# 464421_22-01_BBP.net
KiCad netlist of a schematic drawn in Altium Designer
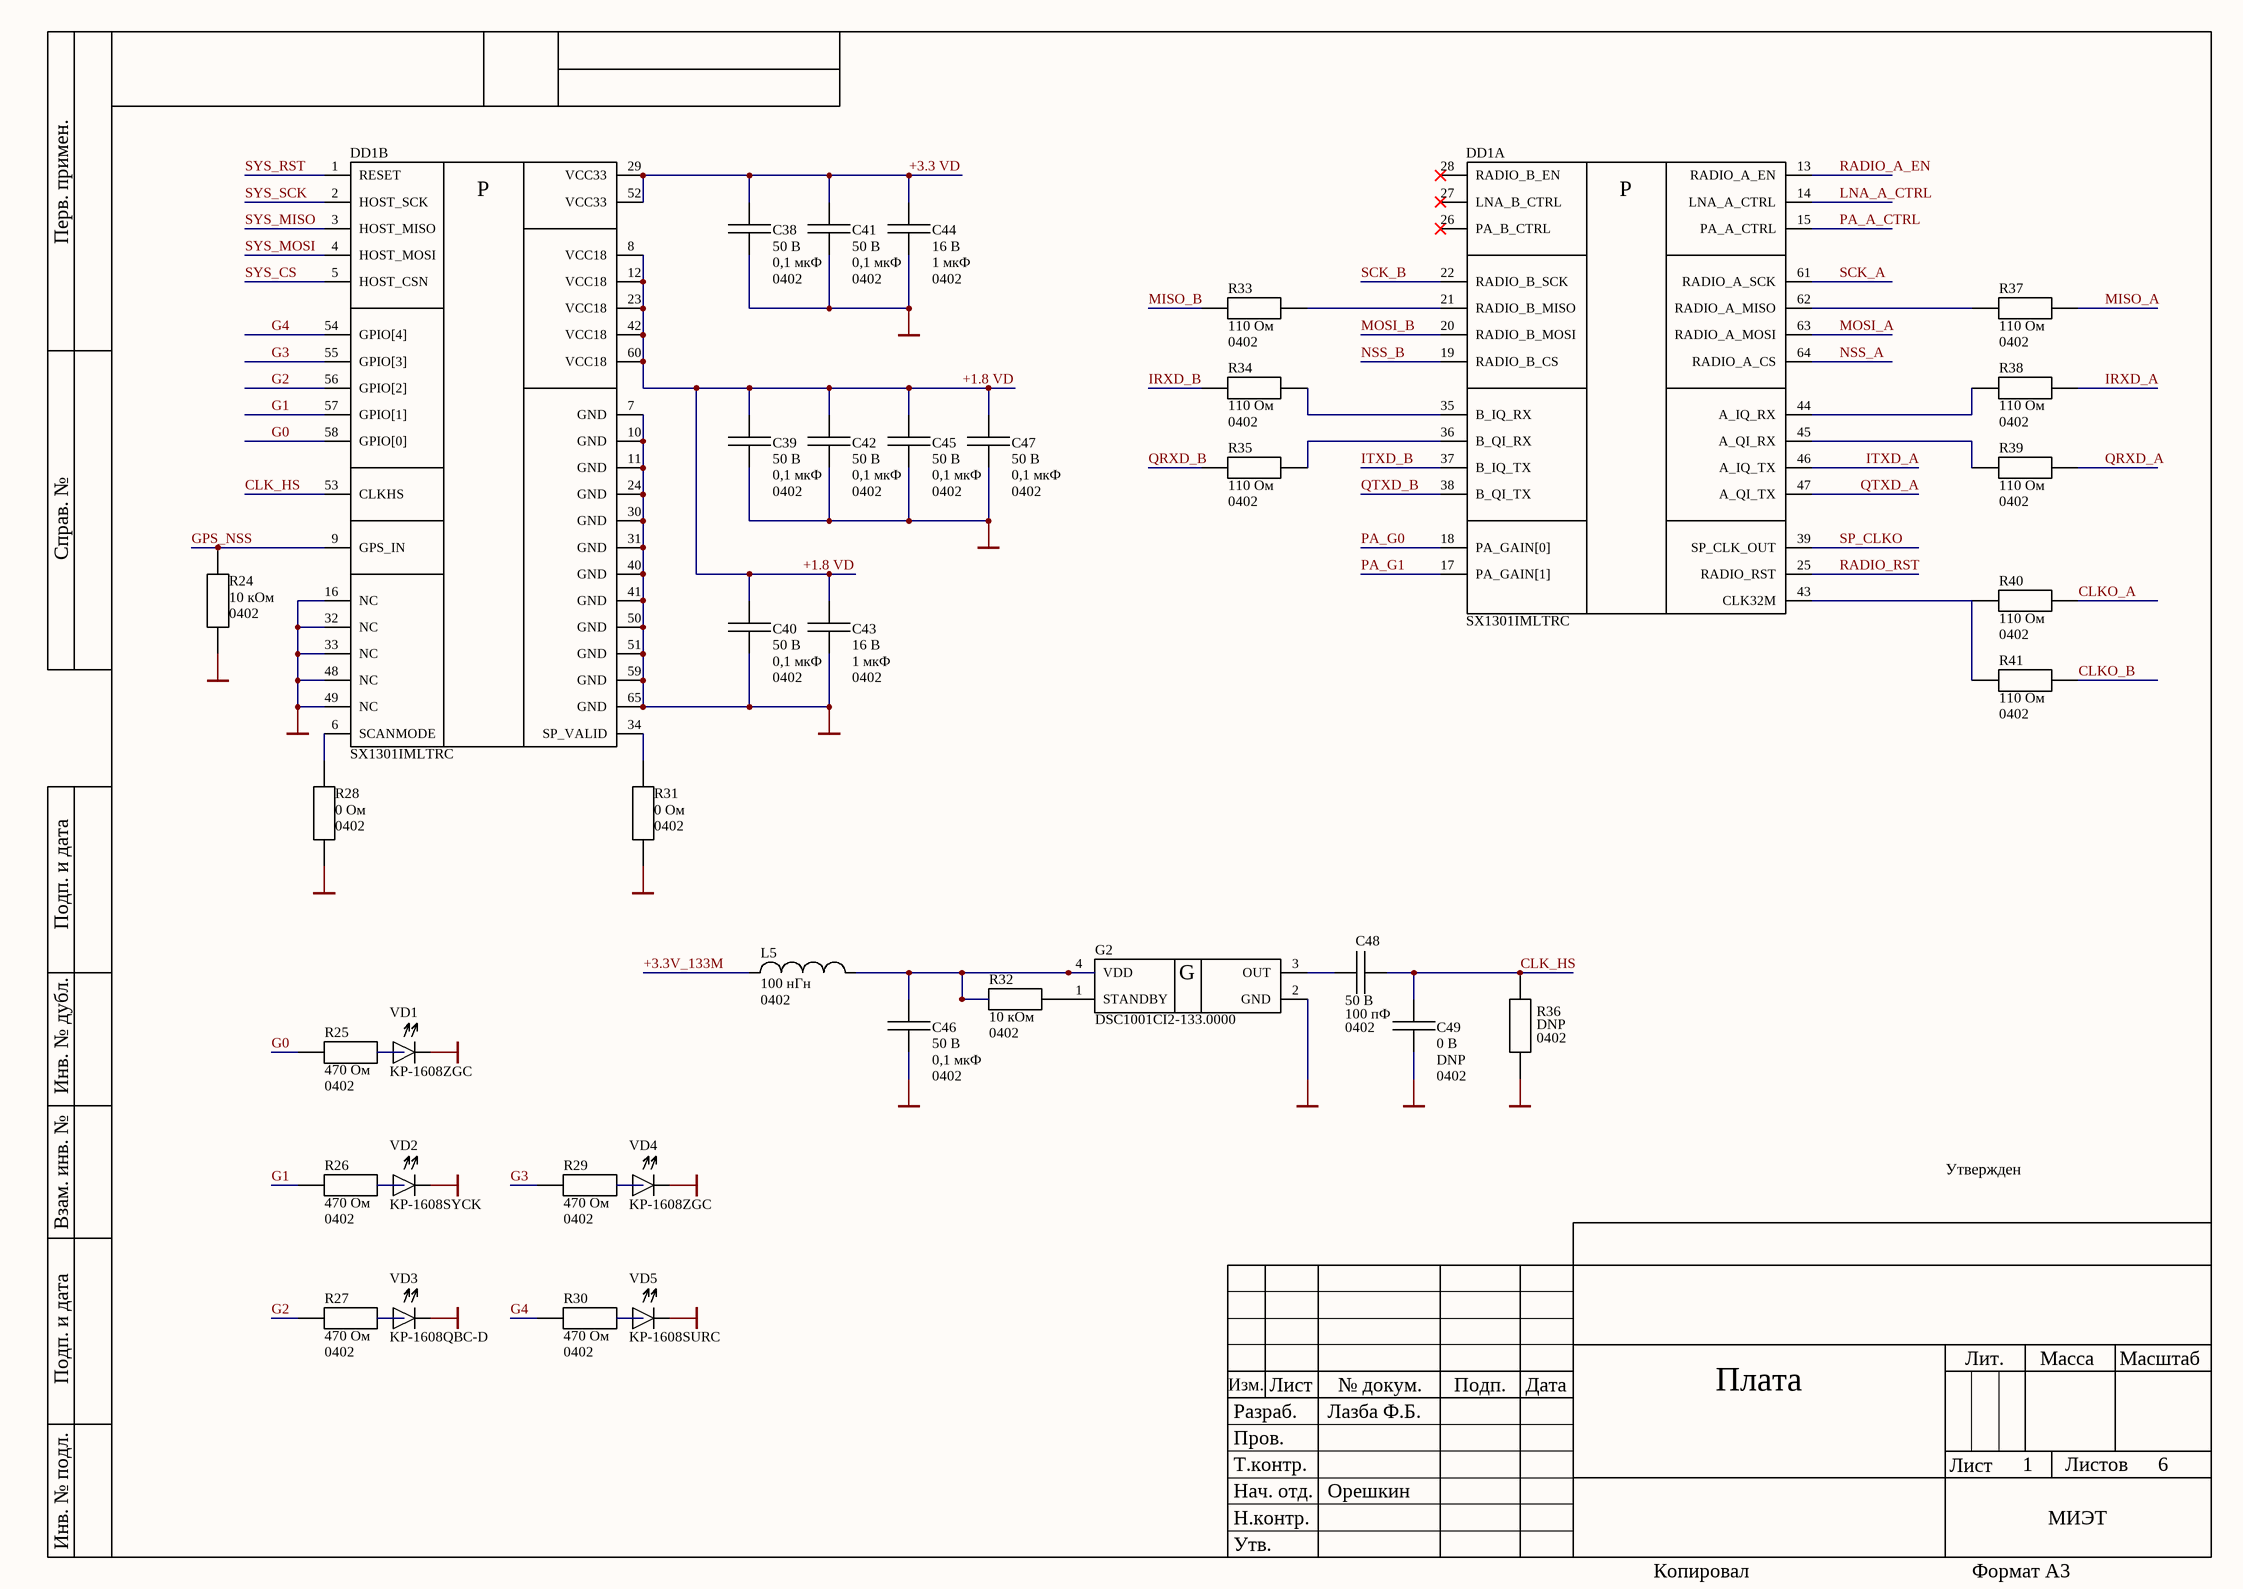
[diagram p0: МПСУ.464421.22-01 BBP.SchDoc]

(export (version "E")
  (design (tool "Eeschema 10.0.6"))
  (components
    (comp (ref "C38")
      (value "0,1 мкФ")
      (footprint "Passive_V2_0:CAPC100X50X55L20N")
      (description "Capacitor 0402")
      (fields
        (field (name "PARTNUMBER") "GRM155R71H104KE14J")
        (field (name "MANUFACTURER") "Murata")
        (field (name "PEAK_CONDITION") "50 В")
        (field (name "PACKAGE") "0402")
        (field (name "DESIGNER") "Свидерский")
      )
      (libsource (lib "Passive_V2_0") (part "C 0402"))
    )
    (comp (ref "C39")
      (value "0,1 мкФ")
      (footprint "Passive_V2_0:CAPC100X50X55L20N")
      (description "Capacitor 0402")
      (fields
        (field (name "PARTNUMBER") "GRM155R71H104KE14J")
        (field (name "MANUFACTURER") "Murata")
        (field (name "PEAK_CONDITION") "50 В")
        (field (name "PACKAGE") "0402")
        (field (name "DESIGNER") "Свидерский")
      )
      (libsource (lib "Passive_V2_0") (part "C 0402"))
    )
    (comp (ref "C40")
      (value "0,1 мкФ")
      (footprint "Passive_V2_0:CAPC100X50X55L20N")
      (description "Capacitor 0402")
      (fields
        (field (name "PARTNUMBER") "GRM155R71H104KE14J")
        (field (name "MANUFACTURER") "Murata")
        (field (name "PEAK_CONDITION") "50 В")
        (field (name "PACKAGE") "0402")
        (field (name "DESIGNER") "Свидерский")
      )
      (libsource (lib "Passive_V2_0") (part "C 0402"))
    )
    (comp (ref "C41")
      (value "0,1 мкФ")
      (footprint "Passive_V2_0:CAPC100X50X55L20N")
      (description "Capacitor 0402")
      (fields
        (field (name "PARTNUMBER") "GRM155R71H104KE14J")
        (field (name "MANUFACTURER") "Murata")
        (field (name "PEAK_CONDITION") "50 В")
        (field (name "PACKAGE") "0402")
        (field (name "DESIGNER") "Свидерский")
      )
      (libsource (lib "Passive_V2_0") (part "C 0402"))
    )
    (comp (ref "C42")
      (value "0,1 мкФ")
      (footprint "Passive_V2_0:CAPC100X50X55L20N")
      (description "Capacitor 0402")
      (fields
        (field (name "PARTNUMBER") "GRM155R71H104KE14J")
        (field (name "MANUFACTURER") "Murata")
        (field (name "PEAK_CONDITION") "50 В")
        (field (name "PACKAGE") "0402")
        (field (name "DESIGNER") "Свидерский")
      )
      (libsource (lib "Passive_V2_0") (part "C 0402"))
    )
    (comp (ref "C43")
      (value "1 мкФ")
      (footprint "Passive_V2_0:CAPC100X50X55L20N")
      (description "Capacitor 0402")
      (fields
        (field (name "PARTNUMBER") "GRM155R61C105KA12D")
        (field (name "MANUFACTURER") "Murata")
        (field (name "PEAK_CONDITION") "16 В")
        (field (name "PACKAGE") "0402")
        (field (name "DESIGNER") "Свидерский")
      )
      (libsource (lib "Passive_V2_0") (part "C 0402"))
    )
    (comp (ref "C44")
      (value "1 мкФ")
      (footprint "Passive_V2_0:CAPC100X50X55L20N")
      (description "Capacitor 0402")
      (fields
        (field (name "PARTNUMBER") "GRM155R61C105KA12D")
        (field (name "MANUFACTURER") "Murata")
        (field (name "PEAK_CONDITION") "16 В")
        (field (name "PACKAGE") "0402")
        (field (name "DESIGNER") "Свидерский")
      )
      (libsource (lib "Passive_V2_0") (part "C 0402"))
    )
    (comp (ref "C45")
      (value "0,1 мкФ")
      (footprint "Passive_V2_0:CAPC100X50X55L20N")
      (description "Capacitor 0402")
      (fields
        (field (name "PARTNUMBER") "GRM155R71H104KE14J")
        (field (name "MANUFACTURER") "Murata")
        (field (name "PEAK_CONDITION") "50 В")
        (field (name "PACKAGE") "0402")
        (field (name "DESIGNER") "Свидерский")
      )
      (libsource (lib "Passive_V2_0") (part "C 0402"))
    )
    (comp (ref "C46")
      (value "0,1 мкФ")
      (footprint "Passive_V2_0:CAPC100X50X55L20N")
      (description "Capacitor 0402")
      (fields
        (field (name "PARTNUMBER") "GRM155R71H104KE14J")
        (field (name "MANUFACTURER") "Murata")
        (field (name "PEAK_CONDITION") "50 В")
        (field (name "PACKAGE") "0402")
        (field (name "DESIGNER") "Свидерский")
      )
      (libsource (lib "Passive_V2_0") (part "C 0402"))
    )
    (comp (ref "C47")
      (value "0,1 мкФ")
      (footprint "Passive_V2_0:CAPC100X50X55L20N")
      (description "Capacitor 0402")
      (fields
        (field (name "PARTNUMBER") "GRM155R71H104KE14J")
        (field (name "MANUFACTURER") "Murata")
        (field (name "PEAK_CONDITION") "50 В")
        (field (name "PACKAGE") "0402")
        (field (name "DESIGNER") "Свидерский")
      )
      (libsource (lib "Passive_V2_0") (part "C 0402"))
    )
    (comp (ref "C48")
      (value "100 пФ")
      (footprint "Passive_V2_0:CAPC100X50X55L20N")
      (description "Capacitor 0402")
      (fields
        (field (name "PARTNUMBER") "GRM1555C1H101JZ01D")
        (field (name "MANUFACTURER") "Murata")
        (field (name "PEAK_CONDITION") "50 В")
        (field (name "PACKAGE") "0402")
        (field (name "DESIGNER") "Свидерский")
      )
      (libsource (lib "Passive_V2_0") (part "C 0402"))
    )
    (comp (ref "C49")
      (value "DNP")
      (footprint "Passive_V2_0:CAPC100X50X55L20N")
      (description "Capacitor 0402")
      (fields
        (field (name "TOLERANCE") "0 %")
        (field (name "PEAK_CONDITION") "0 В")
        (field (name "PACKAGE") "0402")
        (field (name "Comment") "DNP 0402")
        (field (name "DESIGNER") "Свидерский")
      )
      (libsource (lib "Passive_V2_0") (part "C 0402"))
    )
    (comp (ref "DD1")
      (value "SX1301IMLTRC")
      (footprint "IC_V2_0:SX1301IMLTRC")
      (description "LoRa Core™ Digital Baseband Chip for outdoor LoRaWAN® network macro gateways")
      (fields
        (field (name "MANUFACTURER") "Semtech")
        (field (name "PARTNUMBER") "SX1301IMLTRC")
        (field (name "DESIGNER") "Лазба")
      )
      (libsource (lib "IC_V2_0") (part "SX1301IMLTRC"))
    )
    (comp (ref "G2")
      (value "DSC1001CI2-133.0000")
      (footprint "IC_V2_0:DSC1001CI2")
      (description "1.8V-3.3V Low-Power Precision CMOS Oscillators 1-150 MHz Family")
      (fields
        (field (name "MANUFACTURER") "Microchip")
        (field (name "PARTNUMBER") "DSC1001CI2-133.0000")
        (field (name "DESIGNER") "Лазба")
      )
      (libsource (lib "IC_V2_0") (part "DSC1001/3/4***-***.****"))
    )
    (comp (ref "L5")
      (value "100 нГн")
      (footprint "Passive_V2_0:INDC100X50X60L10N")
      (description "Inductor 0402")
      (fields
        (field (name "PARTNUMBER") "LQG15HNR10J02D")
        (field (name "TOLERANCE") "5 %")
        (field (name "PACKAGE") "0402")
        (field (name "DESIGNER") "Свидерский")
      )
      (libsource (lib "Passive_V2_0") (part "L 0402"))
    )
    (comp (ref "R24")
      (value "10 кОм")
      (footprint "Passive_V2_0:RESC100X50X40L25N")
      (description "Resistor 0402")
      (fields
        (field (name "PARTNUMBER") "RI0402L103JT")
        (field (name "TOLERANCE") "5 %")
        (field (name "PACKAGE") "0402")
        (field (name "DESIGNER") "Свидерский")
      )
      (libsource (lib "") (part "R 0402_1"))
    )
    (comp (ref "R25")
      (value "470 Ом")
      (footprint "Passive_V2_0:RESC100X50X40L25N")
      (description "Resistor 0402")
      (fields
        (field (name "PARTNUMBER") "RI0402L471JT")
        (field (name "TOLERANCE") "5 %")
        (field (name "PACKAGE") "0402")
        (field (name "DESIGNER") "Свидерский")
      )
      (libsource (lib "Passive_V2_0") (part "R 0402"))
    )
    (comp (ref "R26")
      (value "470 Ом")
      (footprint "Passive_V2_0:RESC100X50X40L25N")
      (description "Resistor 0402")
      (fields
        (field (name "PARTNUMBER") "RI0402L471JT")
        (field (name "TOLERANCE") "5 %")
        (field (name "PACKAGE") "0402")
        (field (name "DESIGNER") "Свидерский")
      )
      (libsource (lib "Passive_V2_0") (part "R 0402"))
    )
    (comp (ref "R27")
      (value "470 Ом")
      (footprint "Passive_V2_0:RESC100X50X40L25N")
      (description "Resistor 0402")
      (fields
        (field (name "PARTNUMBER") "RI0402L471JT")
        (field (name "TOLERANCE") "5 %")
        (field (name "PACKAGE") "0402")
        (field (name "DESIGNER") "Свидерский")
      )
      (libsource (lib "Passive_V2_0") (part "R 0402"))
    )
    (comp (ref "R28")
      (value "0 Ом")
      (footprint "Passive_V2_0:RESC100X50X40L25N")
      (description "Resistor 0402")
      (fields
        (field (name "PARTNUMBER") "RI0402L000JT")
        (field (name "TOLERANCE") "5 %")
        (field (name "PACKAGE") "0402")
        (field (name "DESIGNER") "Свидерский")
      )
      (libsource (lib "") (part "R 0402_1"))
    )
    (comp (ref "R29")
      (value "470 Ом")
      (footprint "Passive_V2_0:RESC100X50X40L25N")
      (description "Resistor 0402")
      (fields
        (field (name "PARTNUMBER") "RI0402L471JT")
        (field (name "TOLERANCE") "5 %")
        (field (name "PACKAGE") "0402")
        (field (name "DESIGNER") "Свидерский")
      )
      (libsource (lib "Passive_V2_0") (part "R 0402"))
    )
    (comp (ref "R30")
      (value "470 Ом")
      (footprint "Passive_V2_0:RESC100X50X40L25N")
      (description "Resistor 0402")
      (fields
        (field (name "PARTNUMBER") "RI0402L471JT")
        (field (name "TOLERANCE") "5 %")
        (field (name "PACKAGE") "0402")
        (field (name "DESIGNER") "Свидерский")
      )
      (libsource (lib "Passive_V2_0") (part "R 0402"))
    )
    (comp (ref "R31")
      (value "0 Ом")
      (footprint "Passive_V2_0:RESC100X50X40L25N")
      (description "Resistor 0402")
      (fields
        (field (name "PARTNUMBER") "RI0402L000JT")
        (field (name "TOLERANCE") "5 %")
        (field (name "PACKAGE") "0402")
        (field (name "DESIGNER") "Свидерский")
      )
      (libsource (lib "") (part "R 0402_1"))
    )
    (comp (ref "R32")
      (value "10 кОм")
      (footprint "Passive_V2_0:RESC100X50X40L25N")
      (description "Resistor 0402")
      (fields
        (field (name "PARTNUMBER") "RI0402L103JT")
        (field (name "TOLERANCE") "5 %")
        (field (name "PACKAGE") "0402")
        (field (name "DESIGNER") "Свидерский")
      )
      (libsource (lib "Passive_V2_0") (part "R 0402"))
    )
    (comp (ref "R33")
      (value "110 Ом")
      (footprint "Passive_V2_0:RESC100X50X40L25N")
      (description "Resistor 0402")
      (fields
        (field (name "PARTNUMBER") "RC-02U111JT")
        (field (name "TOLERANCE") "5 %")
        (field (name "PACKAGE") "0402")
        (field (name "DESIGNER") "Свидерский")
      )
      (libsource (lib "Passive_V2_0") (part "R 0402"))
    )
    (comp (ref "R34")
      (value "110 Ом")
      (footprint "Passive_V2_0:RESC100X50X40L25N")
      (description "Resistor 0402")
      (fields
        (field (name "PARTNUMBER") "RC-02U111JT")
        (field (name "TOLERANCE") "5 %")
        (field (name "PACKAGE") "0402")
        (field (name "DESIGNER") "Свидерский")
      )
      (libsource (lib "Passive_V2_0") (part "R 0402"))
    )
    (comp (ref "R35")
      (value "110 Ом")
      (footprint "Passive_V2_0:RESC100X50X40L25N")
      (description "Resistor 0402")
      (fields
        (field (name "PARTNUMBER") "RC-02U111JT")
        (field (name "TOLERANCE") "5 %")
        (field (name "PACKAGE") "0402")
        (field (name "DESIGNER") "Свидерский")
      )
      (libsource (lib "Passive_V2_0") (part "R 0402"))
    )
    (comp (ref "R36")
      (value "DNP")
      (footprint "Passive_V2_0:RESC100X50X40L25N")
      (description "Resistor 0402")
      (fields
        (field (name "TOLERANCE") "0 %")
        (field (name "PACKAGE") "0402")
        (field (name "Comment") "DNP 0402")
        (field (name "DESIGNER") "Свидерский")
      )
      (libsource (lib "") (part "R 0402_2"))
    )
    (comp (ref "R37")
      (value "110 Ом")
      (footprint "Passive_V2_0:RESC100X50X40L25N")
      (description "Resistor 0402")
      (fields
        (field (name "PARTNUMBER") "RC-02U111JT")
        (field (name "TOLERANCE") "5 %")
        (field (name "PACKAGE") "0402")
        (field (name "DESIGNER") "Свидерский")
      )
      (libsource (lib "Passive_V2_0") (part "R 0402"))
    )
    (comp (ref "R38")
      (value "110 Ом")
      (footprint "Passive_V2_0:RESC100X50X40L25N")
      (description "Resistor 0402")
      (fields
        (field (name "PARTNUMBER") "RC-02U111JT")
        (field (name "TOLERANCE") "5 %")
        (field (name "PACKAGE") "0402")
        (field (name "DESIGNER") "Свидерский")
      )
      (libsource (lib "Passive_V2_0") (part "R 0402"))
    )
    (comp (ref "R39")
      (value "110 Ом")
      (footprint "Passive_V2_0:RESC100X50X40L25N")
      (description "Resistor 0402")
      (fields
        (field (name "PARTNUMBER") "RC-02U111JT")
        (field (name "TOLERANCE") "5 %")
        (field (name "PACKAGE") "0402")
        (field (name "DESIGNER") "Свидерский")
      )
      (libsource (lib "Passive_V2_0") (part "R 0402"))
    )
    (comp (ref "R40")
      (value "110 Ом")
      (footprint "Passive_V2_0:RESC100X50X40L25N")
      (description "Resistor 0402")
      (fields
        (field (name "PARTNUMBER") "RC-02U111JT")
        (field (name "TOLERANCE") "5 %")
        (field (name "PACKAGE") "0402")
        (field (name "DESIGNER") "Свидерский")
      )
      (libsource (lib "Passive_V2_0") (part "R 0402"))
    )
    (comp (ref "R41")
      (value "110 Ом")
      (footprint "Passive_V2_0:RESC100X50X40L25N")
      (description "Resistor 0402")
      (fields
        (field (name "PARTNUMBER") "RC-02U111JT")
        (field (name "TOLERANCE") "5 %")
        (field (name "PACKAGE") "0402")
        (field (name "DESIGNER") "Свидерский")
      )
      (libsource (lib "Passive_V2_0") (part "R 0402"))
    )
    (comp (ref "VD1")
      (value "KP-1608ZGC")
      (footprint "Discrete_V2_0:KP-1608ZGC")
      (description "1.6X0.8mm SMD CHIP LED LAMP")
      (fields
        (field (name "MANUFACTURER") "Kingbright")
        (field (name "PARTNUMBER") "KP-1608ZGC")
        (field (name "DESIGNER") "Ушакова")
      )
      (libsource (lib "Discrete_V2_0") (part "KP-1608***"))
    )
    (comp (ref "VD2")
      (value "KP-1608SYCK")
      (footprint "Discrete_V2_0:KP-1608ZGC")
      (description "1.6X0.8mm SMD CHIP LED LAMP")
      (fields
        (field (name "MANUFACTURER") "Kingbright")
        (field (name "PARTNUMBER") "KP-1608SYCK")
        (field (name "DESIGNER") "Ушакова")
      )
      (libsource (lib "Discrete_V2_0") (part "KP-1608***"))
    )
    (comp (ref "VD3")
      (value "KP-1608QBC-D")
      (footprint "Discrete_V2_0:KP-1608ZGC")
      (description "1.6X0.8mm SMD CHIP LED LAMP")
      (fields
        (field (name "MANUFACTURER") "Kingbright")
        (field (name "PARTNUMBER") "KP-1608QBC-D")
        (field (name "DESIGNER") "Ушакова")
      )
      (libsource (lib "Discrete_V2_0") (part "KP-1608***"))
    )
    (comp (ref "VD4")
      (value "KP-1608ZGC")
      (footprint "Discrete_V2_0:KP-1608ZGC")
      (description "1.6X0.8mm SMD CHIP LED LAMP")
      (fields
        (field (name "MANUFACTURER") "Kingbright")
        (field (name "PARTNUMBER") "KP-1608ZGC")
        (field (name "DESIGNER") "Ушакова")
      )
      (libsource (lib "Discrete_V2_0") (part "KP-1608***"))
    )
    (comp (ref "VD5")
      (value "KP-1608SURC")
      (footprint "Discrete_V2_0:KP-1608ZGC")
      (description "1.6X0.8mm SMD CHIP LED LAMP")
      (fields
        (field (name "MANUFACTURER") "Kingbright")
        (field (name "PARTNUMBER") "KP-1608SURC")
        (field (name "DESIGNER") "Ушакова")
      )
      (libsource (lib "Discrete_V2_0") (part "KP-1608***"))
    )
  )
  (nets
    (net (code "1") (name "/+1.8 VD") (class "Default")
      (node (ref "C39") (pin "1") (pinfunction "1_1") (pintype "passive"))
      (node (ref "C40") (pin "1") (pinfunction "1_1") (pintype "passive"))
      (node (ref "C42") (pin "1") (pinfunction "1_1") (pintype "passive"))
      (node (ref "C43") (pin "1") (pinfunction "1_1") (pintype "passive"))
      (node (ref "C45") (pin "1") (pinfunction "1_1") (pintype "passive"))
      (node (ref "C47") (pin "1") (pinfunction "1_1") (pintype "passive"))
      (node (ref "DD1") (pin "12") (pinfunction "VCC18_12") (pintype "passive"))
      (node (ref "DD1") (pin "23") (pinfunction "VCC18_23") (pintype "passive"))
      (node (ref "DD1") (pin "42") (pinfunction "VCC18_42") (pintype "passive"))
      (node (ref "DD1") (pin "60") (pinfunction "VCC18_60") (pintype "passive"))
      (node (ref "DD1") (pin "8") (pinfunction "VCC18_8") (pintype "passive"))
    )
    (net (code "2") (name "/+3.3 VD") (class "Default")
      (node (ref "C38") (pin "1") (pinfunction "1_1") (pintype "passive"))
      (node (ref "C41") (pin "1") (pinfunction "1_1") (pintype "passive"))
      (node (ref "C44") (pin "1") (pinfunction "1_1") (pintype "passive"))
      (node (ref "DD1") (pin "29") (pinfunction "VCC33_29") (pintype "passive"))
      (node (ref "DD1") (pin "52") (pinfunction "VCC33_52") (pintype "passive"))
    )
    (net (code "3") (name "/+3.3V_133M") (class "Default")
      (node (ref "L5") (pin "1") (pinfunction "1_1") (pintype "passive"))
    )
    (net (code "4") (name "/CLKO_A") (class "Default")
      (node (ref "R40") (pin "2") (pinfunction "2_2") (pintype "passive"))
    )
    (net (code "5") (name "/CLKO_B") (class "Default")
      (node (ref "R41") (pin "2") (pinfunction "2_2") (pintype "passive"))
    )
    (net (code "6") (name "/CLK_HS") (class "Default")
      (node (ref "C48") (pin "2") (pinfunction "2_2") (pintype "passive"))
      (node (ref "C49") (pin "1") (pinfunction "1_1") (pintype "passive"))
      (node (ref "DD1") (pin "53") (pinfunction "CLKHS_53") (pintype "passive"))
      (node (ref "R36") (pin "1") (pinfunction "1_1") (pintype "passive"))
    )
    (net (code "7") (name "/G0") (class "Default")
      (node (ref "DD1") (pin "58") (pinfunction "GPIO[0]_58") (pintype "passive"))
      (node (ref "R25") (pin "1") (pinfunction "1_1") (pintype "passive"))
    )
    (net (code "8") (name "/G1") (class "Default")
      (node (ref "DD1") (pin "57") (pinfunction "GPIO[1]_57") (pintype "passive"))
      (node (ref "R26") (pin "1") (pinfunction "1_1") (pintype "passive"))
    )
    (net (code "9") (name "/G2") (class "Default")
      (node (ref "DD1") (pin "56") (pinfunction "GPIO[2]_56") (pintype "passive"))
      (node (ref "R27") (pin "1") (pinfunction "1_1") (pintype "passive"))
    )
    (net (code "10") (name "/G3") (class "Default")
      (node (ref "DD1") (pin "55") (pinfunction "GPIO[3]_55") (pintype "passive"))
      (node (ref "R29") (pin "1") (pinfunction "1_1") (pintype "passive"))
    )
    (net (code "11") (name "/G4") (class "Default")
      (node (ref "DD1") (pin "54") (pinfunction "GPIO[4]_54") (pintype "passive"))
      (node (ref "R30") (pin "1") (pinfunction "1_1") (pintype "passive"))
    )
    (net (code "12") (name "/GPS_NSS") (class "Default")
      (node (ref "DD1") (pin "9") (pinfunction "GPS_IN_9") (pintype "passive"))
      (node (ref "R24") (pin "2") (pinfunction "2_2") (pintype "passive"))
    )
    (net (code "13") (name "/IRXD_A") (class "Default")
      (node (ref "R38") (pin "2") (pinfunction "2_2") (pintype "passive"))
    )
    (net (code "14") (name "/IRXD_B") (class "Default")
      (node (ref "R34") (pin "1") (pinfunction "1_1") (pintype "passive"))
    )
    (net (code "15") (name "/ITXD_A") (class "Default")
      (node (ref "DD1") (pin "46") (pinfunction "A_IQ_TX_46") (pintype "passive"))
    )
    (net (code "16") (name "/ITXD_B") (class "Default")
      (node (ref "DD1") (pin "37") (pinfunction "B_IQ_TX_37") (pintype "passive"))
    )
    (net (code "17") (name "/LNA_A_CTRL") (class "Default")
      (node (ref "DD1") (pin "14") (pinfunction "LNA_A_CTRL_14") (pintype "passive"))
    )
    (net (code "18") (name "/MISO_A") (class "Default")
      (node (ref "R37") (pin "2") (pinfunction "2_2") (pintype "passive"))
    )
    (net (code "19") (name "/MISO_B") (class "Default")
      (node (ref "R33") (pin "1") (pinfunction "1_1") (pintype "passive"))
    )
    (net (code "20") (name "/MOSI_A") (class "Default")
      (node (ref "DD1") (pin "63") (pinfunction "RADIO_A_MOSI_63") (pintype "passive"))
    )
    (net (code "21") (name "/MOSI_B") (class "Default")
      (node (ref "DD1") (pin "20") (pinfunction "RADIO_B_MOSI_20") (pintype "passive"))
    )
    (net (code "22") (name "/NSS_A") (class "Default")
      (node (ref "DD1") (pin "64") (pinfunction "RADIO_A_CS_64") (pintype "passive"))
    )
    (net (code "23") (name "/NSS_B") (class "Default")
      (node (ref "DD1") (pin "19") (pinfunction "RADIO_B_CS_19") (pintype "passive"))
    )
    (net (code "24") (name "/PA_A_CTRL") (class "Default")
      (node (ref "DD1") (pin "15") (pinfunction "PA_A_CTRL_15") (pintype "passive"))
    )
    (net (code "25") (name "/PA_G0") (class "Default")
      (node (ref "DD1") (pin "18") (pinfunction "PA_GAIN[0]_18") (pintype "passive"))
    )
    (net (code "26") (name "/PA_G1") (class "Default")
      (node (ref "DD1") (pin "17") (pinfunction "PA_GAIN[1]_17") (pintype "passive"))
    )
    (net (code "27") (name "/QRXD_A") (class "Default")
      (node (ref "R39") (pin "2") (pinfunction "2_2") (pintype "passive"))
    )
    (net (code "28") (name "/QRXD_B") (class "Default")
      (node (ref "R35") (pin "1") (pinfunction "1_1") (pintype "passive"))
    )
    (net (code "29") (name "/QTXD_A") (class "Default")
      (node (ref "DD1") (pin "47") (pinfunction "A_QI_TX_47") (pintype "passive"))
    )
    (net (code "30") (name "/QTXD_B") (class "Default")
      (node (ref "DD1") (pin "38") (pinfunction "B_QI_TX_38") (pintype "passive"))
    )
    (net (code "31") (name "/RADIO_A_EN") (class "Default")
      (node (ref "DD1") (pin "13") (pinfunction "RADIO_A_EN_13") (pintype "passive"))
    )
    (net (code "32") (name "/RADIO_RST") (class "Default")
      (node (ref "DD1") (pin "25") (pinfunction "RADIO_RST_25") (pintype "passive"))
    )
    (net (code "33") (name "/SCK_A") (class "Default")
      (node (ref "DD1") (pin "61") (pinfunction "RADIO_A_SCK_61") (pintype "passive"))
    )
    (net (code "34") (name "/SCK_B") (class "Default")
      (node (ref "DD1") (pin "22") (pinfunction "RADIO_B_SCK_22") (pintype "passive"))
    )
    (net (code "35") (name "/SP_CLKO") (class "Default")
      (node (ref "DD1") (pin "39") (pinfunction "SP_CLK_OUT_39") (pintype "passive"))
    )
    (net (code "36") (name "/SYS_CS") (class "Default")
      (node (ref "DD1") (pin "5") (pinfunction "HOST_CSN_5") (pintype "passive"))
    )
    (net (code "37") (name "/SYS_MISO") (class "Default")
      (node (ref "DD1") (pin "3") (pinfunction "HOST_MISO_3") (pintype "passive"))
    )
    (net (code "38") (name "/SYS_MOSI") (class "Default")
      (node (ref "DD1") (pin "4") (pinfunction "HOST_MOSI_4") (pintype "passive"))
    )
    (net (code "39") (name "/SYS_RST") (class "Default")
      (node (ref "DD1") (pin "1") (pinfunction "RESET_1") (pintype "passive"))
    )
    (net (code "40") (name "/SYS_SCK") (class "Default")
      (node (ref "DD1") (pin "2") (pinfunction "HOST_SCK_2") (pintype "passive"))
    )
    (net (code "41") (name "GND") (class "Default")
      (node (ref "C38") (pin "2") (pinfunction "2_2") (pintype "passive"))
      (node (ref "C39") (pin "2") (pinfunction "2_2") (pintype "passive"))
      (node (ref "C40") (pin "2") (pinfunction "2_2") (pintype "passive"))
      (node (ref "C41") (pin "2") (pinfunction "2_2") (pintype "passive"))
      (node (ref "C42") (pin "2") (pinfunction "2_2") (pintype "passive"))
      (node (ref "C43") (pin "2") (pinfunction "2_2") (pintype "passive"))
      (node (ref "C44") (pin "2") (pinfunction "2_2") (pintype "passive"))
      (node (ref "C45") (pin "2") (pinfunction "2_2") (pintype "passive"))
      (node (ref "C46") (pin "2") (pinfunction "2_2") (pintype "passive"))
      (node (ref "C47") (pin "2") (pinfunction "2_2") (pintype "passive"))
      (node (ref "C49") (pin "2") (pinfunction "2_2") (pintype "passive"))
      (node (ref "DD1") (pin "10") (pinfunction "GND_10") (pintype "passive"))
      (node (ref "DD1") (pin "11") (pinfunction "GND_11") (pintype "passive"))
      (node (ref "DD1") (pin "16") (pinfunction "NC_16") (pintype "passive"))
      (node (ref "DD1") (pin "24") (pinfunction "GND_24") (pintype "passive"))
      (node (ref "DD1") (pin "30") (pinfunction "GND_30") (pintype "passive"))
      (node (ref "DD1") (pin "31") (pinfunction "GND_31") (pintype "passive"))
      (node (ref "DD1") (pin "32") (pinfunction "NC_32") (pintype "passive"))
      (node (ref "DD1") (pin "33") (pinfunction "NC_33") (pintype "passive"))
      (node (ref "DD1") (pin "40") (pinfunction "GND_40") (pintype "passive"))
      (node (ref "DD1") (pin "41") (pinfunction "GND_41") (pintype "passive"))
      (node (ref "DD1") (pin "48") (pinfunction "NC_48") (pintype "passive"))
      (node (ref "DD1") (pin "49") (pinfunction "NC_49") (pintype "passive"))
      (node (ref "DD1") (pin "50") (pinfunction "GND_50") (pintype "passive"))
      (node (ref "DD1") (pin "51") (pinfunction "GND_51") (pintype "passive"))
      (node (ref "DD1") (pin "59") (pinfunction "GND_59") (pintype "passive"))
      (node (ref "DD1") (pin "65") (pinfunction "GND_65") (pintype "passive"))
      (node (ref "DD1") (pin "7") (pinfunction "GND_7") (pintype "passive"))
      (node (ref "G2") (pin "2") (pinfunction "GND_2") (pintype "passive"))
      (node (ref "R24") (pin "1") (pinfunction "1_1") (pintype "passive"))
      (node (ref "R28") (pin "1") (pinfunction "1_1") (pintype "passive"))
      (node (ref "R31") (pin "1") (pinfunction "1_1") (pintype "passive"))
      (node (ref "R36") (pin "2") (pinfunction "2_2") (pintype "passive"))
      (node (ref "VD1") (pin "2") (pinfunction "2_2") (pintype "passive"))
      (node (ref "VD2") (pin "2") (pinfunction "2_2") (pintype "passive"))
      (node (ref "VD3") (pin "2") (pinfunction "2_2") (pintype "passive"))
      (node (ref "VD4") (pin "2") (pinfunction "2_2") (pintype "passive"))
      (node (ref "VD5") (pin "2") (pinfunction "2_2") (pintype "passive"))
    )
    (net (code "42") (name "Net-(DD1A-A_IQ_RX)") (class "Default")
      (node (ref "DD1") (pin "44") (pinfunction "A_IQ_RX_44") (pintype "passive"))
      (node (ref "R38") (pin "1") (pinfunction "1_1") (pintype "passive"))
    )
    (net (code "43") (name "Net-(DD1A-A_QI_RX)") (class "Default")
      (node (ref "DD1") (pin "45") (pinfunction "A_QI_RX_45") (pintype "passive"))
      (node (ref "R39") (pin "1") (pinfunction "1_1") (pintype "passive"))
    )
    (net (code "44") (name "Net-(DD1A-B_IQ_RX)") (class "Default")
      (node (ref "DD1") (pin "35") (pinfunction "B_IQ_RX_35") (pintype "passive"))
      (node (ref "R34") (pin "2") (pinfunction "2_2") (pintype "passive"))
    )
    (net (code "45") (name "Net-(DD1A-B_QI_RX)") (class "Default")
      (node (ref "DD1") (pin "36") (pinfunction "B_QI_RX_36") (pintype "passive"))
      (node (ref "R35") (pin "2") (pinfunction "2_2") (pintype "passive"))
    )
    (net (code "46") (name "Net-(DD1A-CLK32M)") (class "Default")
      (node (ref "DD1") (pin "43") (pinfunction "CLK32M_43") (pintype "passive"))
      (node (ref "R40") (pin "1") (pinfunction "1_1") (pintype "passive"))
      (node (ref "R41") (pin "1") (pinfunction "1_1") (pintype "passive"))
    )
    (net (code "47") (name "Net-(DD1A-RADIO_A_MISO)") (class "Default")
      (node (ref "DD1") (pin "62") (pinfunction "RADIO_A_MISO_62") (pintype "passive"))
      (node (ref "R37") (pin "1") (pinfunction "1_1") (pintype "passive"))
    )
    (net (code "48") (name "Net-(DD1A-RADIO_B_MISO)") (class "Default")
      (node (ref "DD1") (pin "21") (pinfunction "RADIO_B_MISO_21") (pintype "passive"))
      (node (ref "R33") (pin "2") (pinfunction "2_2") (pintype "passive"))
    )
    (net (code "49") (name "Net-(DD1B-SCANMODE)") (class "Default")
      (node (ref "DD1") (pin "6") (pinfunction "SCANMODE_6") (pintype "passive"))
      (node (ref "R28") (pin "2") (pinfunction "2_2") (pintype "passive"))
    )
    (net (code "50") (name "Net-(DD1B-SP_VALID)") (class "Default")
      (node (ref "DD1") (pin "34") (pinfunction "SP_VALID_34") (pintype "passive"))
      (node (ref "R31") (pin "2") (pinfunction "2_2") (pintype "passive"))
    )
    (net (code "51") (name "Net-(G2-OUT)") (class "Default")
      (node (ref "C48") (pin "1") (pinfunction "1_1") (pintype "passive"))
      (node (ref "G2") (pin "3") (pinfunction "OUT_3") (pintype "passive"))
    )
    (net (code "52") (name "Net-(G2-STANDBY)") (class "Default")
      (node (ref "G2") (pin "1") (pinfunction "STANDBY_1") (pintype "passive"))
      (node (ref "R32") (pin "2") (pinfunction "2_2") (pintype "passive"))
    )
    (net (code "53") (name "Net-(G2-VDD)") (class "Default")
      (node (ref "C46") (pin "1") (pinfunction "1_1") (pintype "passive"))
      (node (ref "G2") (pin "4") (pinfunction "VDD_4") (pintype "passive"))
      (node (ref "L5") (pin "2") (pinfunction "2_2") (pintype "passive"))
      (node (ref "R32") (pin "1") (pinfunction "1_1") (pintype "passive"))
    )
    (net (code "54") (name "Net-(R25-Pad2)") (class "Default")
      (node (ref "R25") (pin "2") (pinfunction "2_2") (pintype "passive"))
      (node (ref "VD1") (pin "1") (pinfunction "1_1") (pintype "passive"))
    )
    (net (code "55") (name "Net-(R26-Pad2)") (class "Default")
      (node (ref "R26") (pin "2") (pinfunction "2_2") (pintype "passive"))
      (node (ref "VD2") (pin "1") (pinfunction "1_1") (pintype "passive"))
    )
    (net (code "56") (name "Net-(R27-Pad2)") (class "Default")
      (node (ref "R27") (pin "2") (pinfunction "2_2") (pintype "passive"))
      (node (ref "VD3") (pin "1") (pinfunction "1_1") (pintype "passive"))
    )
    (net (code "57") (name "Net-(R29-Pad2)") (class "Default")
      (node (ref "R29") (pin "2") (pinfunction "2_2") (pintype "passive"))
      (node (ref "VD4") (pin "1") (pinfunction "1_1") (pintype "passive"))
    )
    (net (code "58") (name "Net-(R30-Pad2)") (class "Default")
      (node (ref "R30") (pin "2") (pinfunction "2_2") (pintype "passive"))
      (node (ref "VD5") (pin "1") (pinfunction "1_1") (pintype "passive"))
    )
    (net (code "59") (name "unconnected-(DD1A-LNA_B_CTRL-Pad27)") (class "Default")
      (node (ref "DD1") (pin "27") (pinfunction "LNA_B_CTRL_27") (pintype "passive+no_connect"))
    )
    (net (code "60") (name "unconnected-(DD1A-PA_B_CTRL-Pad26)") (class "Default")
      (node (ref "DD1") (pin "26") (pinfunction "PA_B_CTRL_26") (pintype "passive+no_connect"))
    )
    (net (code "61") (name "unconnected-(DD1A-RADIO_B_EN-Pad28)") (class "Default")
      (node (ref "DD1") (pin "28") (pinfunction "RADIO_B_EN_28") (pintype "passive+no_connect"))
    )
  )
)
